# HYDRA_V3_TEMPLATE.net
KiCad netlist of a schematic drawn in Altium Designer
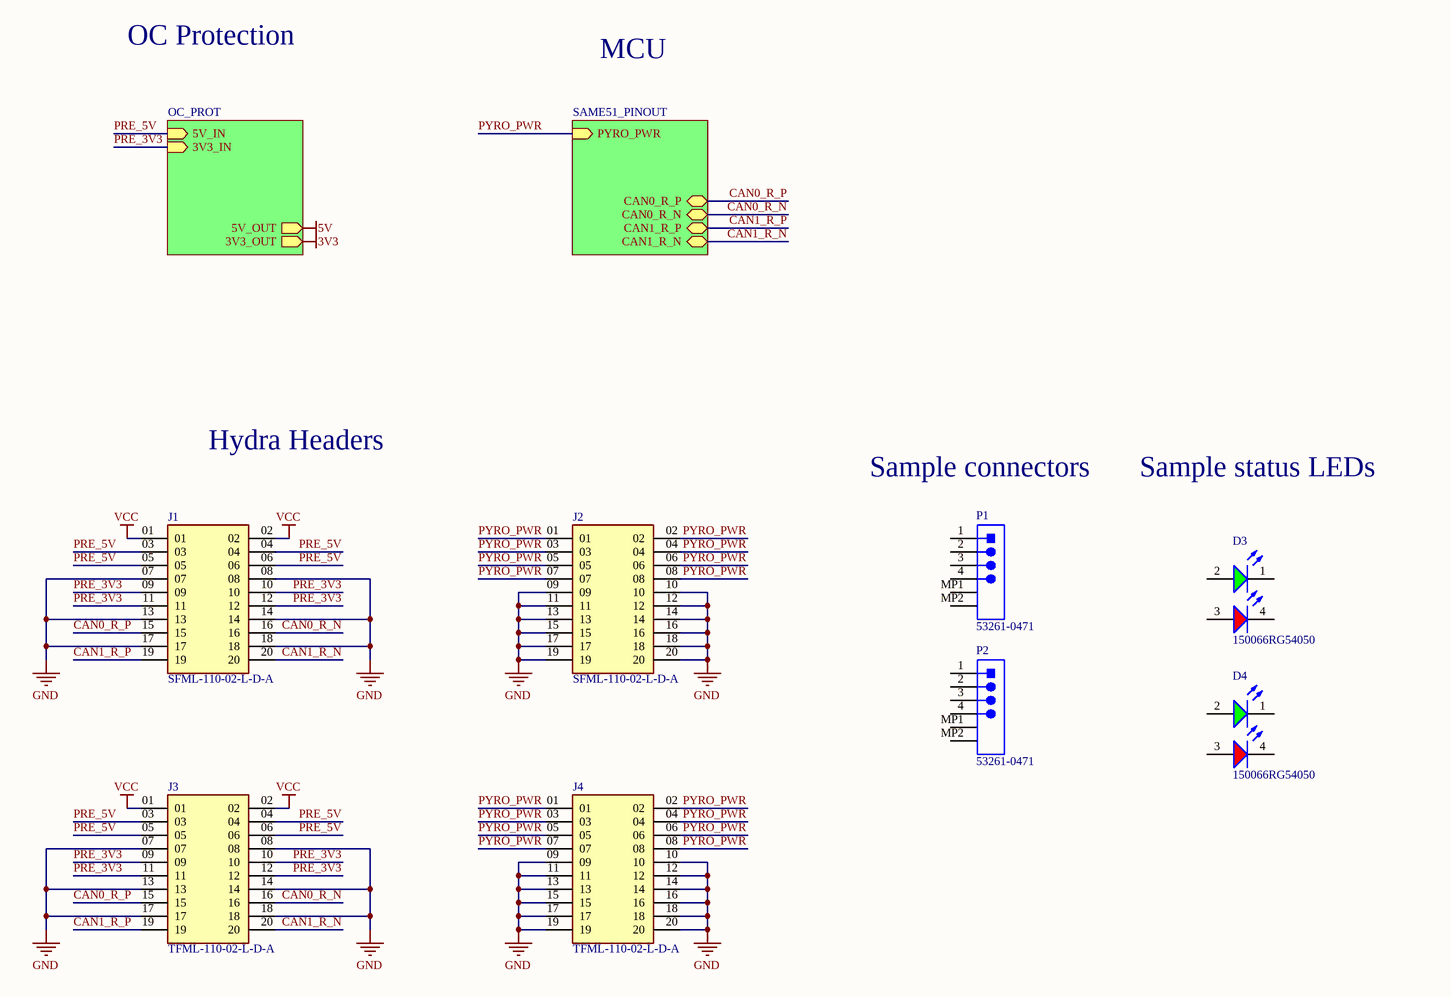
[diagram p0: HYDRA_V3_TEMPLATE.SchDoc]

(export (version "E")
  (design (tool "Eeschema 10.0.6"))
  (components
    (comp (ref "D3")
      (value "150066RG54050")
      (footprint "WL-SBCD_0606")
      (description "Led, Red/Grn, 180Mcd/230Mcd, 624Nm/525Nm Rohs Compliant: Yes")
      (libsource (lib "uORocketry Hardware") (part "WL-SBCD_0606_Red & Green"))
    )
    (comp (ref "D4")
      (value "150066RG54050")
      (footprint "WL-SBCD_0606")
      (description "Led, Red/Grn, 180Mcd/230Mcd, 624Nm/525Nm Rohs Compliant: Yes")
      (libsource (lib "uORocketry Hardware") (part "WL-SBCD_0606_Red & Green"))
    )
    (comp (ref "J1")
      (value "SFML-110-02-L-D-A")
      (footprint "SFML-110-02-L-D-A-Footprint-1")
      (description "Headers & Wire Housings .050 Tiger Eye High-Reliability Locking Socket Strip")
      (libsource (lib "uORocketry Hardware") (part "SFML-110-02-L-D-A"))
    )
    (comp (ref "J2")
      (value "SFML-110-02-L-D-A")
      (footprint "SFML-110-02-L-D-A-Footprint-1")
      (description "Headers & Wire Housings .050 Tiger Eye High-Reliability Locking Socket Strip")
      (libsource (lib "uORocketry Hardware") (part "SFML-110-02-L-D-A"))
    )
    (comp (ref "J3")
      (value "TFML-110-02-L-D-A")
      (footprint "TFML-110-02-L-D-A-Footprint-1")
      (description "Conn Shrouded Header (4 Sides) HDR 20 POS 1.27mm Solder ST Top Entry SMD TIGER EYE™ Tube")
      (libsource (lib "uORocketry Hardware") (part "TFML-110-02-L-D-A"))
    )
    (comp (ref "J4")
      (value "TFML-110-02-L-D-A")
      (footprint "TFML-110-02-L-D-A-Footprint-1")
      (description "Conn Shrouded Header (4 Sides) HDR 20 POS 1.27mm Solder ST Top Entry SMD TIGER EYE™ Tube")
      (libsource (lib "uORocketry Hardware") (part "TFML-110-02-L-D-A"))
    )
    (comp (ref "P1")
      (value "53261-0471")
      (footprint "MOLEX-53261-0471_V")
      (description "Male Header, Pitch 1.25 mm, 1 x 4 Position, Height 3.4 mm, -40 to 85 degC, RoHS, Tape and Reel")
      (fields (field (name "MANUFACTURER") "Molex"))
      (libsource (lib "Altium Content Vault") (part "CN-1P-2M-R4_A"))
    )
    (comp (ref "P2")
      (value "53261-0471")
      (footprint "MOLEX-53261-0471_V")
      (description "Male Header, Pitch 1.25 mm, 1 x 4 Position, Height 3.4 mm, -40 to 85 degC, RoHS, Tape and Reel")
      (fields (field (name "MANUFACTURER") "Molex"))
      (libsource (lib "Altium Content Vault") (part "CN-1P-2M-R4_A"))
    )
  )
  (nets
    (net (code "1") (name "/CAN0_R_N") (class "Default")
      (node (ref "J1") (pin "16") (pinfunction "16_16") (pintype "passive"))
      (node (ref "J3") (pin "16") (pinfunction "16_16") (pintype "passive"))
    )
    (net (code "2") (name "/CAN0_R_P") (class "Default")
      (node (ref "J1") (pin "15") (pinfunction "15_15") (pintype "passive"))
      (node (ref "J3") (pin "15") (pinfunction "15_15") (pintype "passive"))
    )
    (net (code "3") (name "/CAN1_R_N") (class "Default")
      (node (ref "J1") (pin "20") (pinfunction "20_20") (pintype "passive"))
      (node (ref "J3") (pin "20") (pinfunction "20_20") (pintype "passive"))
    )
    (net (code "4") (name "/CAN1_R_P") (class "Default")
      (node (ref "J1") (pin "19") (pinfunction "19_19") (pintype "passive"))
      (node (ref "J3") (pin "19") (pinfunction "19_19") (pintype "passive"))
    )
    (net (code "5") (name "/PRE_3V3") (class "Default")
      (node (ref "J1") (pin "09") (pinfunction "09_09") (pintype "passive"))
      (node (ref "J1") (pin "10") (pinfunction "10_10") (pintype "passive"))
      (node (ref "J1") (pin "11") (pinfunction "11_11") (pintype "passive"))
      (node (ref "J1") (pin "12") (pinfunction "12_12") (pintype "passive"))
      (node (ref "J3") (pin "09") (pinfunction "09_09") (pintype "passive"))
      (node (ref "J3") (pin "10") (pinfunction "10_10") (pintype "passive"))
      (node (ref "J3") (pin "11") (pinfunction "11_11") (pintype "passive"))
      (node (ref "J3") (pin "12") (pinfunction "12_12") (pintype "passive"))
    )
    (net (code "6") (name "/PRE_5V") (class "Default")
      (node (ref "J1") (pin "03") (pinfunction "03_03") (pintype "passive"))
      (node (ref "J1") (pin "04") (pinfunction "04_04") (pintype "passive"))
      (node (ref "J1") (pin "05") (pinfunction "05_05") (pintype "passive"))
      (node (ref "J1") (pin "06") (pinfunction "06_06") (pintype "passive"))
      (node (ref "J3") (pin "03") (pinfunction "03_03") (pintype "passive"))
      (node (ref "J3") (pin "04") (pinfunction "04_04") (pintype "passive"))
      (node (ref "J3") (pin "05") (pinfunction "05_05") (pintype "passive"))
      (node (ref "J3") (pin "06") (pinfunction "06_06") (pintype "passive"))
    )
    (net (code "7") (name "/PYRO_PWR") (class "Default")
      (node (ref "J2") (pin "01") (pinfunction "01_01") (pintype "passive"))
      (node (ref "J2") (pin "02") (pinfunction "02_02") (pintype "passive"))
      (node (ref "J2") (pin "03") (pinfunction "03_03") (pintype "passive"))
      (node (ref "J2") (pin "04") (pinfunction "04_04") (pintype "passive"))
      (node (ref "J2") (pin "05") (pinfunction "05_05") (pintype "passive"))
      (node (ref "J2") (pin "06") (pinfunction "06_06") (pintype "passive"))
      (node (ref "J2") (pin "07") (pinfunction "07_07") (pintype "passive"))
      (node (ref "J2") (pin "08") (pinfunction "08_08") (pintype "passive"))
      (node (ref "J4") (pin "01") (pinfunction "01_01") (pintype "passive"))
      (node (ref "J4") (pin "02") (pinfunction "02_02") (pintype "passive"))
      (node (ref "J4") (pin "03") (pinfunction "03_03") (pintype "passive"))
      (node (ref "J4") (pin "04") (pinfunction "04_04") (pintype "passive"))
      (node (ref "J4") (pin "05") (pinfunction "05_05") (pintype "passive"))
      (node (ref "J4") (pin "06") (pinfunction "06_06") (pintype "passive"))
      (node (ref "J4") (pin "07") (pinfunction "07_07") (pintype "passive"))
      (node (ref "J4") (pin "08") (pinfunction "08_08") (pintype "passive"))
    )
    (net (code "10") (name "GND") (class "Default")
      (node (ref "J1") (pin "07") (pinfunction "07_07") (pintype "passive"))
      (node (ref "J1") (pin "08") (pinfunction "08_08") (pintype "passive"))
      (node (ref "J1") (pin "13") (pinfunction "13_13") (pintype "passive"))
      (node (ref "J1") (pin "14") (pinfunction "14_14") (pintype "passive"))
      (node (ref "J1") (pin "17") (pinfunction "17_17") (pintype "passive"))
      (node (ref "J1") (pin "18") (pinfunction "18_18") (pintype "passive"))
      (node (ref "J2") (pin "09") (pinfunction "09_09") (pintype "passive"))
      (node (ref "J2") (pin "10") (pinfunction "10_10") (pintype "passive"))
      (node (ref "J2") (pin "11") (pinfunction "11_11") (pintype "passive"))
      (node (ref "J2") (pin "12") (pinfunction "12_12") (pintype "passive"))
      (node (ref "J2") (pin "13") (pinfunction "13_13") (pintype "passive"))
      (node (ref "J2") (pin "14") (pinfunction "14_14") (pintype "passive"))
      (node (ref "J2") (pin "15") (pinfunction "15_15") (pintype "passive"))
      (node (ref "J2") (pin "16") (pinfunction "16_16") (pintype "passive"))
      (node (ref "J2") (pin "17") (pinfunction "17_17") (pintype "passive"))
      (node (ref "J2") (pin "18") (pinfunction "18_18") (pintype "passive"))
      (node (ref "J2") (pin "19") (pinfunction "19_19") (pintype "passive"))
      (node (ref "J2") (pin "20") (pinfunction "20_20") (pintype "passive"))
      (node (ref "J3") (pin "07") (pinfunction "07_07") (pintype "passive"))
      (node (ref "J3") (pin "08") (pinfunction "08_08") (pintype "passive"))
      (node (ref "J3") (pin "13") (pinfunction "13_13") (pintype "passive"))
      (node (ref "J3") (pin "14") (pinfunction "14_14") (pintype "passive"))
      (node (ref "J3") (pin "17") (pinfunction "17_17") (pintype "passive"))
      (node (ref "J3") (pin "18") (pinfunction "18_18") (pintype "passive"))
      (node (ref "J4") (pin "09") (pinfunction "09_09") (pintype "passive"))
      (node (ref "J4") (pin "10") (pinfunction "10_10") (pintype "passive"))
      (node (ref "J4") (pin "11") (pinfunction "11_11") (pintype "passive"))
      (node (ref "J4") (pin "12") (pinfunction "12_12") (pintype "passive"))
      (node (ref "J4") (pin "13") (pinfunction "13_13") (pintype "passive"))
      (node (ref "J4") (pin "14") (pinfunction "14_14") (pintype "passive"))
      (node (ref "J4") (pin "15") (pinfunction "15_15") (pintype "passive"))
      (node (ref "J4") (pin "16") (pinfunction "16_16") (pintype "passive"))
      (node (ref "J4") (pin "17") (pinfunction "17_17") (pintype "passive"))
      (node (ref "J4") (pin "18") (pinfunction "18_18") (pintype "passive"))
      (node (ref "J4") (pin "19") (pinfunction "19_19") (pintype "passive"))
      (node (ref "J4") (pin "20") (pinfunction "20_20") (pintype "passive"))
    )
    (net (code "11") (name "VCC") (class "Default")
      (node (ref "J1") (pin "01") (pinfunction "01_01") (pintype "passive"))
      (node (ref "J1") (pin "02") (pinfunction "02_02") (pintype "passive"))
      (node (ref "J3") (pin "01") (pinfunction "01_01") (pintype "passive"))
      (node (ref "J3") (pin "02") (pinfunction "02_02") (pintype "passive"))
    )
    (net (code "12") (name "unconnected-(D3-A-Pad2)") (class "Default")
      (node (ref "D3") (pin "2") (pinfunction "A_2") (pintype "passive"))
    )
    (net (code "13") (name "unconnected-(D3-A-Pad3)") (class "Default")
      (node (ref "D3") (pin "3") (pinfunction "A_3") (pintype "passive"))
    )
    (net (code "14") (name "unconnected-(D3-K-Pad1)") (class "Default")
      (node (ref "D3") (pin "1") (pinfunction "K_1") (pintype "passive"))
    )
    (net (code "15") (name "unconnected-(D3-K-Pad4)") (class "Default")
      (node (ref "D3") (pin "4") (pinfunction "K_4") (pintype "passive"))
    )
    (net (code "16") (name "unconnected-(D4-A-Pad2)") (class "Default")
      (node (ref "D4") (pin "2") (pinfunction "A_2") (pintype "passive"))
    )
    (net (code "17") (name "unconnected-(D4-A-Pad3)") (class "Default")
      (node (ref "D4") (pin "3") (pinfunction "A_3") (pintype "passive"))
    )
    (net (code "18") (name "unconnected-(D4-K-Pad1)") (class "Default")
      (node (ref "D4") (pin "1") (pinfunction "K_1") (pintype "passive"))
    )
    (net (code "19") (name "unconnected-(D4-K-Pad4)") (class "Default")
      (node (ref "D4") (pin "4") (pinfunction "K_4") (pintype "passive"))
    )
    (net (code "20") (name "unconnected-(P1-Pad1)") (class "Default")
      (node (ref "P1") (pin "1") (pinfunction "1_1") (pintype "passive"))
    )
    (net (code "21") (name "unconnected-(P1-Pad2)") (class "Default")
      (node (ref "P1") (pin "2") (pinfunction "2_2") (pintype "passive"))
    )
    (net (code "22") (name "unconnected-(P1-Pad3)") (class "Default")
      (node (ref "P1") (pin "3") (pinfunction "3_3") (pintype "passive"))
    )
    (net (code "23") (name "unconnected-(P1-Pad4)") (class "Default")
      (node (ref "P1") (pin "4") (pinfunction "4_4") (pintype "passive"))
    )
    (net (code "24") (name "unconnected-(P1-PadMP1)") (class "Default")
      (node (ref "P1") (pin "MP1") (pinfunction "MP1_MP1") (pintype "passive"))
    )
    (net (code "25") (name "unconnected-(P1-PadMP2)") (class "Default")
      (node (ref "P1") (pin "MP2") (pinfunction "MP2_MP2") (pintype "passive"))
    )
    (net (code "26") (name "unconnected-(P2-Pad1)") (class "Default")
      (node (ref "P2") (pin "1") (pinfunction "1_1") (pintype "passive"))
    )
    (net (code "27") (name "unconnected-(P2-Pad2)") (class "Default")
      (node (ref "P2") (pin "2") (pinfunction "2_2") (pintype "passive"))
    )
    (net (code "28") (name "unconnected-(P2-Pad3)") (class "Default")
      (node (ref "P2") (pin "3") (pinfunction "3_3") (pintype "passive"))
    )
    (net (code "29") (name "unconnected-(P2-Pad4)") (class "Default")
      (node (ref "P2") (pin "4") (pinfunction "4_4") (pintype "passive"))
    )
    (net (code "30") (name "unconnected-(P2-PadMP1)") (class "Default")
      (node (ref "P2") (pin "MP1") (pinfunction "MP1_MP1") (pintype "passive"))
    )
    (net (code "31") (name "unconnected-(P2-PadMP2)") (class "Default")
      (node (ref "P2") (pin "MP2") (pinfunction "MP2_MP2") (pintype "passive"))
    )
  )
)
